# PCD-disc-schematic.net
KiCad netlist of a schematic drawn in Altium Designer
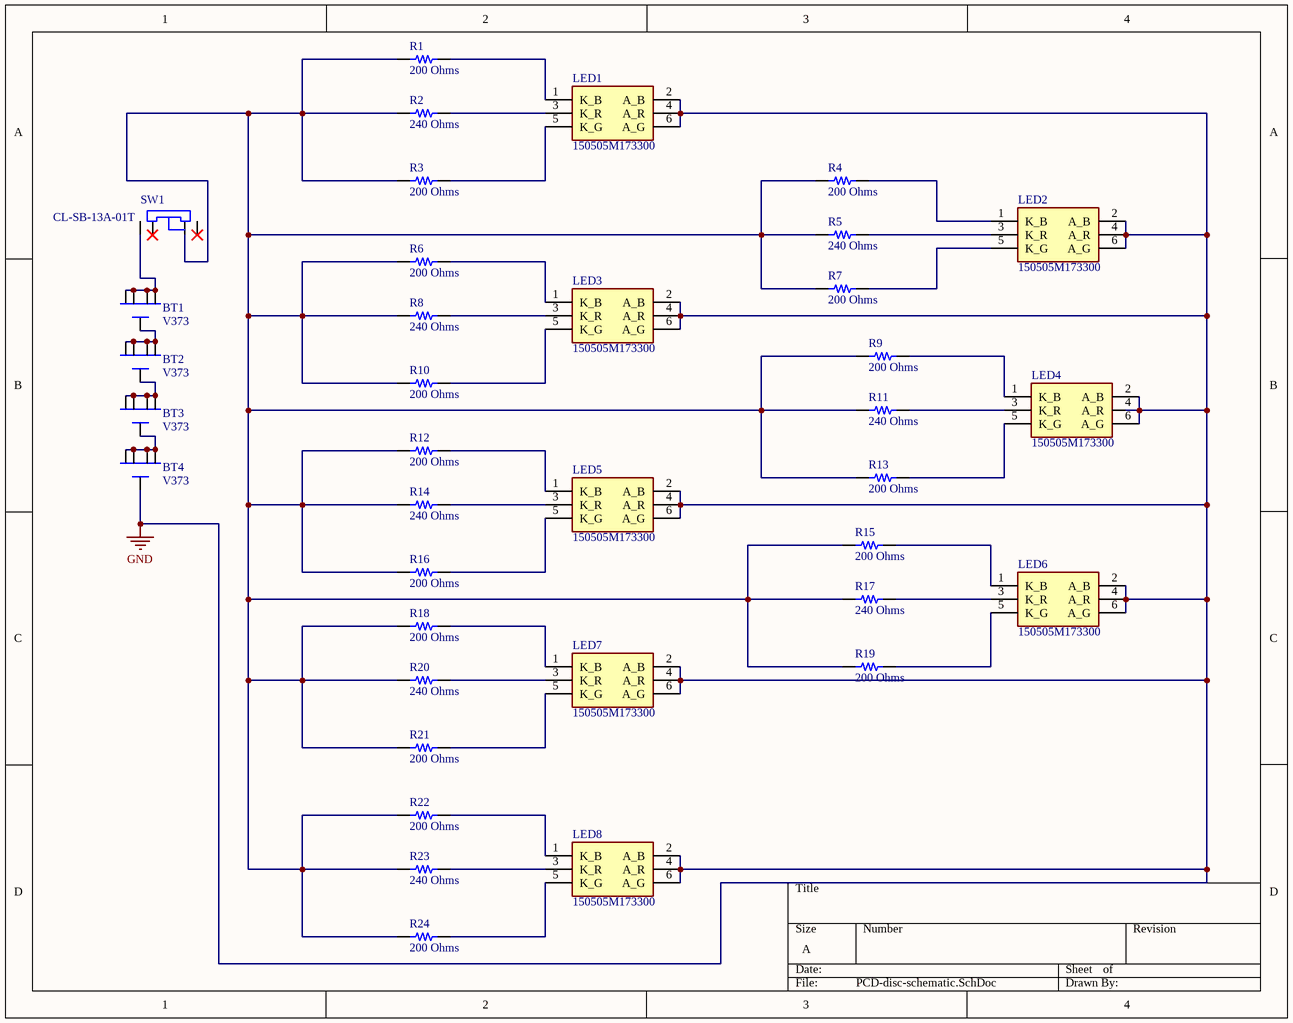
[diagram p0: PCD-disc-schematic.SchDoc]

(export (version "E")
  (design (tool "Eeschema 10.0.6"))
  (components
    (comp (ref "BT1") (value "V373") (footprint "V373") (libsource (lib "PCD-lib") (part "V373")))
    (comp (ref "BT2") (value "V373") (footprint "V373") (libsource (lib "PCD-lib") (part "V373")))
    (comp (ref "BT3") (value "V373") (footprint "V373") (libsource (lib "PCD-lib") (part "V373")))
    (comp (ref "BT4") (value "V373") (footprint "V373") (libsource (lib "PCD-lib") (part "V373")))
    (comp (ref "LED1")
      (value "150505M173300")
      (footprint "SamacSys:150505M173300")
      (description "LED")
      (fields (field (name "MOUSER PART NUMBER") "710-150505M173300"))
      (libsource (lib "*") (part "150505M173300"))
    )
    (comp (ref "LED2")
      (value "150505M173300")
      (footprint "SamacSys:150505M173300")
      (description "LED")
      (fields (field (name "MOUSER PART NUMBER") "710-150505M173300"))
      (libsource (lib "*") (part "150505M173300"))
    )
    (comp (ref "LED3")
      (value "150505M173300")
      (footprint "SamacSys:150505M173300")
      (description "LED")
      (fields (field (name "MOUSER PART NUMBER") "710-150505M173300"))
      (libsource (lib "*") (part "150505M173300"))
    )
    (comp (ref "LED4")
      (value "150505M173300")
      (footprint "SamacSys:150505M173300")
      (description "LED")
      (fields (field (name "MOUSER PART NUMBER") "710-150505M173300"))
      (libsource (lib "*") (part "150505M173300"))
    )
    (comp (ref "LED5")
      (value "150505M173300")
      (footprint "SamacSys:150505M173300")
      (description "LED")
      (fields (field (name "MOUSER PART NUMBER") "710-150505M173300"))
      (libsource (lib "*") (part "150505M173300"))
    )
    (comp (ref "LED6")
      (value "150505M173300")
      (footprint "SamacSys:150505M173300")
      (description "LED")
      (fields (field (name "MOUSER PART NUMBER") "710-150505M173300"))
      (libsource (lib "*") (part "150505M173300"))
    )
    (comp (ref "LED7")
      (value "150505M173300")
      (footprint "SamacSys:150505M173300")
      (description "LED")
      (fields (field (name "MOUSER PART NUMBER") "710-150505M173300"))
      (libsource (lib "*") (part "150505M173300"))
    )
    (comp (ref "LED8")
      (value "150505M173300")
      (footprint "SamacSys:150505M173300")
      (description "LED")
      (fields (field (name "MOUSER PART NUMBER") "710-150505M173300"))
      (libsource (lib "*") (part "150505M173300"))
    )
    (comp (ref "R1")
      (value "200 Ohms")
      (footprint "RES 0603_1608")
      (description "RES 200 OHM 1% 1/10W 0603")
      (fields (field (name "PART NUMBER") "CRCW0603200RFKEAC") (field (name "MANUFACTURER") "Vishay Dale"))
      (libsource (lib "Celestial Altium Library - altium_library") (part "Resistor"))
    )
    (comp (ref "R2")
      (value "240 Ohms")
      (footprint "RES 0603_1608")
      (description "RES 240 OHM 1% 1/10W 0603")
      (fields
        (field (name "PART NUMBER") "RMCF0603FT240R")
        (field (name "MANUFACTURER") "Stackpole Electronics Inc")
      )
      (libsource (lib "Celestial Altium Library - altium_library") (part "Resistor"))
    )
    (comp (ref "R3")
      (value "200 Ohms")
      (footprint "RES 0603_1608")
      (description "RES 200 OHM 1% 1/10W 0603")
      (fields (field (name "PART NUMBER") "CRCW0603200RFKEAC") (field (name "MANUFACTURER") "Vishay Dale"))
      (libsource (lib "Celestial Altium Library - altium_library") (part "Resistor"))
    )
    (comp (ref "R4")
      (value "200 Ohms")
      (footprint "RES 0603_1608")
      (description "RES 200 OHM 1% 1/10W 0603")
      (fields (field (name "PART NUMBER") "CRCW0603200RFKEAC") (field (name "MANUFACTURER") "Vishay Dale"))
      (libsource (lib "Celestial Altium Library - altium_library") (part "Resistor"))
    )
    (comp (ref "R5")
      (value "240 Ohms")
      (footprint "RES 0603_1608")
      (description "RES 240 OHM 1% 1/10W 0603")
      (fields
        (field (name "PART NUMBER") "RMCF0603FT240R")
        (field (name "MANUFACTURER") "Stackpole Electronics Inc")
      )
      (libsource (lib "Celestial Altium Library - altium_library") (part "Resistor"))
    )
    (comp (ref "R6")
      (value "200 Ohms")
      (footprint "RES 0603_1608")
      (description "RES 200 OHM 1% 1/10W 0603")
      (fields (field (name "PART NUMBER") "CRCW0603200RFKEAC") (field (name "MANUFACTURER") "Vishay Dale"))
      (libsource (lib "Celestial Altium Library - altium_library") (part "Resistor"))
    )
    (comp (ref "R7")
      (value "200 Ohms")
      (footprint "RES 0603_1608")
      (description "RES 200 OHM 1% 1/10W 0603")
      (fields (field (name "PART NUMBER") "CRCW0603200RFKEAC") (field (name "MANUFACTURER") "Vishay Dale"))
      (libsource (lib "Celestial Altium Library - altium_library") (part "Resistor"))
    )
    (comp (ref "R8")
      (value "240 Ohms")
      (footprint "RES 0603_1608")
      (description "RES 240 OHM 1% 1/10W 0603")
      (fields
        (field (name "PART NUMBER") "RMCF0603FT240R")
        (field (name "MANUFACTURER") "Stackpole Electronics Inc")
      )
      (libsource (lib "Celestial Altium Library - altium_library") (part "Resistor"))
    )
    (comp (ref "R9")
      (value "200 Ohms")
      (footprint "RES 0603_1608")
      (description "RES 200 OHM 1% 1/10W 0603")
      (fields (field (name "PART NUMBER") "CRCW0603200RFKEAC") (field (name "MANUFACTURER") "Vishay Dale"))
      (libsource (lib "Celestial Altium Library - altium_library") (part "Resistor"))
    )
    (comp (ref "R10")
      (value "200 Ohms")
      (footprint "RES 0603_1608")
      (description "RES 200 OHM 1% 1/10W 0603")
      (fields (field (name "PART NUMBER") "CRCW0603200RFKEAC") (field (name "MANUFACTURER") "Vishay Dale"))
      (libsource (lib "Celestial Altium Library - altium_library") (part "Resistor"))
    )
    (comp (ref "R11")
      (value "240 Ohms")
      (footprint "RES 0603_1608")
      (description "RES 240 OHM 1% 1/10W 0603")
      (fields
        (field (name "PART NUMBER") "RMCF0603FT240R")
        (field (name "MANUFACTURER") "Stackpole Electronics Inc")
      )
      (libsource (lib "Celestial Altium Library - altium_library") (part "Resistor"))
    )
    (comp (ref "R12")
      (value "200 Ohms")
      (footprint "RES 0603_1608")
      (description "RES 200 OHM 1% 1/10W 0603")
      (fields (field (name "PART NUMBER") "CRCW0603200RFKEAC") (field (name "MANUFACTURER") "Vishay Dale"))
      (libsource (lib "Celestial Altium Library - altium_library") (part "Resistor"))
    )
    (comp (ref "R13")
      (value "200 Ohms")
      (footprint "RES 0603_1608")
      (description "RES 200 OHM 1% 1/10W 0603")
      (fields (field (name "PART NUMBER") "CRCW0603200RFKEAC") (field (name "MANUFACTURER") "Vishay Dale"))
      (libsource (lib "Celestial Altium Library - altium_library") (part "Resistor"))
    )
    (comp (ref "R14")
      (value "240 Ohms")
      (footprint "RES 0603_1608")
      (description "RES 240 OHM 1% 1/10W 0603")
      (fields
        (field (name "PART NUMBER") "RMCF0603FT240R")
        (field (name "MANUFACTURER") "Stackpole Electronics Inc")
      )
      (libsource (lib "Celestial Altium Library - altium_library") (part "Resistor"))
    )
    (comp (ref "R15")
      (value "200 Ohms")
      (footprint "RES 0603_1608")
      (description "RES 200 OHM 1% 1/10W 0603")
      (fields (field (name "PART NUMBER") "CRCW0603200RFKEAC") (field (name "MANUFACTURER") "Vishay Dale"))
      (libsource (lib "Celestial Altium Library - altium_library") (part "Resistor"))
    )
    (comp (ref "R16")
      (value "200 Ohms")
      (footprint "RES 0603_1608")
      (description "RES 200 OHM 1% 1/10W 0603")
      (fields (field (name "PART NUMBER") "CRCW0603200RFKEAC") (field (name "MANUFACTURER") "Vishay Dale"))
      (libsource (lib "Celestial Altium Library - altium_library") (part "Resistor"))
    )
    (comp (ref "R17")
      (value "240 Ohms")
      (footprint "RES 0603_1608")
      (description "RES 240 OHM 1% 1/10W 0603")
      (fields
        (field (name "PART NUMBER") "RMCF0603FT240R")
        (field (name "MANUFACTURER") "Stackpole Electronics Inc")
      )
      (libsource (lib "Celestial Altium Library - altium_library") (part "Resistor"))
    )
    (comp (ref "R18")
      (value "200 Ohms")
      (footprint "RES 0603_1608")
      (description "RES 200 OHM 1% 1/10W 0603")
      (fields (field (name "PART NUMBER") "CRCW0603200RFKEAC") (field (name "MANUFACTURER") "Vishay Dale"))
      (libsource (lib "Celestial Altium Library - altium_library") (part "Resistor"))
    )
    (comp (ref "R19")
      (value "200 Ohms")
      (footprint "RES 0603_1608")
      (description "RES 200 OHM 1% 1/10W 0603")
      (fields (field (name "PART NUMBER") "CRCW0603200RFKEAC") (field (name "MANUFACTURER") "Vishay Dale"))
      (libsource (lib "Celestial Altium Library - altium_library") (part "Resistor"))
    )
    (comp (ref "R20")
      (value "240 Ohms")
      (footprint "RES 0603_1608")
      (description "RES 240 OHM 1% 1/10W 0603")
      (fields
        (field (name "PART NUMBER") "RMCF0603FT240R")
        (field (name "MANUFACTURER") "Stackpole Electronics Inc")
      )
      (libsource (lib "Celestial Altium Library - altium_library") (part "Resistor"))
    )
    (comp (ref "R21")
      (value "200 Ohms")
      (footprint "RES 0603_1608")
      (description "RES 200 OHM 1% 1/10W 0603")
      (fields (field (name "PART NUMBER") "CRCW0603200RFKEAC") (field (name "MANUFACTURER") "Vishay Dale"))
      (libsource (lib "Celestial Altium Library - altium_library") (part "Resistor"))
    )
    (comp (ref "R22")
      (value "200 Ohms")
      (footprint "RES 0603_1608")
      (description "RES 200 OHM 1% 1/10W 0603")
      (fields (field (name "PART NUMBER") "CRCW0603200RFKEAC") (field (name "MANUFACTURER") "Vishay Dale"))
      (libsource (lib "Celestial Altium Library - altium_library") (part "Resistor"))
    )
    (comp (ref "R23")
      (value "240 Ohms")
      (footprint "RES 0603_1608")
      (description "RES 240 OHM 1% 1/10W 0603")
      (fields
        (field (name "PART NUMBER") "RMCF0603FT240R")
        (field (name "MANUFACTURER") "Stackpole Electronics Inc")
      )
      (libsource (lib "Celestial Altium Library - altium_library") (part "Resistor"))
    )
    (comp (ref "R24")
      (value "200 Ohms")
      (footprint "RES 0603_1608")
      (description "RES 200 OHM 1% 1/10W 0603")
      (fields (field (name "PART NUMBER") "CRCW0603200RFKEAC") (field (name "MANUFACTURER") "Vishay Dale"))
      (libsource (lib "Celestial Altium Library - altium_library") (part "Resistor"))
    )
    (comp (ref "SW1")
      (value "CL-SB-13A-01T")
      (footprint "CL-SB-13A-01T")
      (description "SWITCH SLIDE SP3T 200MA 12V")
      (libsource (lib "PCD-lib") (part "CL-SB-13A-01T"))
    )
  )
  (nets
    (net (code "1") (name "GND") (class "Default")
      (node (ref "BT4") (pin "5") (pinfunction "5_5") (pintype "passive"))
      (node (ref "LED1") (pin "2") (pinfunction "A_B_2") (pintype "passive"))
      (node (ref "LED1") (pin "4") (pinfunction "A_R_4") (pintype "passive"))
      (node (ref "LED1") (pin "6") (pinfunction "A_G_6") (pintype "passive"))
      (node (ref "LED2") (pin "2") (pinfunction "A_B_2") (pintype "passive"))
      (node (ref "LED2") (pin "4") (pinfunction "A_R_4") (pintype "passive"))
      (node (ref "LED2") (pin "6") (pinfunction "A_G_6") (pintype "passive"))
      (node (ref "LED3") (pin "2") (pinfunction "A_B_2") (pintype "passive"))
      (node (ref "LED3") (pin "4") (pinfunction "A_R_4") (pintype "passive"))
      (node (ref "LED3") (pin "6") (pinfunction "A_G_6") (pintype "passive"))
      (node (ref "LED4") (pin "2") (pinfunction "A_B_2") (pintype "passive"))
      (node (ref "LED4") (pin "4") (pinfunction "A_R_4") (pintype "passive"))
      (node (ref "LED4") (pin "6") (pinfunction "A_G_6") (pintype "passive"))
      (node (ref "LED5") (pin "2") (pinfunction "A_B_2") (pintype "passive"))
      (node (ref "LED5") (pin "4") (pinfunction "A_R_4") (pintype "passive"))
      (node (ref "LED5") (pin "6") (pinfunction "A_G_6") (pintype "passive"))
      (node (ref "LED6") (pin "2") (pinfunction "A_B_2") (pintype "passive"))
      (node (ref "LED6") (pin "4") (pinfunction "A_R_4") (pintype "passive"))
      (node (ref "LED6") (pin "6") (pinfunction "A_G_6") (pintype "passive"))
      (node (ref "LED7") (pin "2") (pinfunction "A_B_2") (pintype "passive"))
      (node (ref "LED7") (pin "4") (pinfunction "A_R_4") (pintype "passive"))
      (node (ref "LED7") (pin "6") (pinfunction "A_G_6") (pintype "passive"))
      (node (ref "LED8") (pin "2") (pinfunction "A_B_2") (pintype "passive"))
      (node (ref "LED8") (pin "4") (pinfunction "A_R_4") (pintype "passive"))
      (node (ref "LED8") (pin "6") (pinfunction "A_G_6") (pintype "passive"))
    )
    (net (code "2") (name "Net-(BT1-Pad1)") (class "Default")
      (node (ref "BT1") (pin "1") (pinfunction "1_1") (pintype "passive"))
      (node (ref "BT1") (pin "2") (pinfunction "2_2") (pintype "passive"))
      (node (ref "BT1") (pin "3") (pinfunction "3_3") (pintype "passive"))
      (node (ref "BT1") (pin "4") (pinfunction "4_4") (pintype "passive"))
      (node (ref "SW1") (pin "1") (pinfunction "1_1") (pintype "passive"))
    )
    (net (code "3") (name "Net-(BT1-Pad5)") (class "Default")
      (node (ref "BT1") (pin "5") (pinfunction "5_5") (pintype "passive"))
      (node (ref "BT2") (pin "1") (pinfunction "1_1") (pintype "passive"))
      (node (ref "BT2") (pin "2") (pinfunction "2_2") (pintype "passive"))
      (node (ref "BT2") (pin "3") (pinfunction "3_3") (pintype "passive"))
      (node (ref "BT2") (pin "4") (pinfunction "4_4") (pintype "passive"))
    )
    (net (code "4") (name "Net-(BT2-Pad5)") (class "Default")
      (node (ref "BT2") (pin "5") (pinfunction "5_5") (pintype "passive"))
      (node (ref "BT3") (pin "1") (pinfunction "1_1") (pintype "passive"))
      (node (ref "BT3") (pin "2") (pinfunction "2_2") (pintype "passive"))
      (node (ref "BT3") (pin "3") (pinfunction "3_3") (pintype "passive"))
      (node (ref "BT3") (pin "4") (pinfunction "4_4") (pintype "passive"))
    )
    (net (code "5") (name "Net-(BT3-Pad5)") (class "Default")
      (node (ref "BT3") (pin "5") (pinfunction "5_5") (pintype "passive"))
      (node (ref "BT4") (pin "1") (pinfunction "1_1") (pintype "passive"))
      (node (ref "BT4") (pin "2") (pinfunction "2_2") (pintype "passive"))
      (node (ref "BT4") (pin "3") (pinfunction "3_3") (pintype "passive"))
      (node (ref "BT4") (pin "4") (pinfunction "4_4") (pintype "passive"))
    )
    (net (code "6") (name "Net-(LED1-K_B)") (class "Default")
      (node (ref "LED1") (pin "1") (pinfunction "K_B_1") (pintype "passive"))
      (node (ref "R1") (pin "2") (pinfunction "2_2") (pintype "passive"))
    )
    (net (code "7") (name "Net-(LED1-K_G)") (class "Default")
      (node (ref "LED1") (pin "5") (pinfunction "K_G_5") (pintype "passive"))
      (node (ref "R3") (pin "2") (pinfunction "2_2") (pintype "passive"))
    )
    (net (code "8") (name "Net-(LED1-K_R)") (class "Default")
      (node (ref "LED1") (pin "3") (pinfunction "K_R_3") (pintype "passive"))
      (node (ref "R2") (pin "2") (pinfunction "2_2") (pintype "passive"))
    )
    (net (code "9") (name "Net-(LED2-K_B)") (class "Default")
      (node (ref "LED2") (pin "1") (pinfunction "K_B_1") (pintype "passive"))
      (node (ref "R4") (pin "2") (pinfunction "2_2") (pintype "passive"))
    )
    (net (code "10") (name "Net-(LED2-K_G)") (class "Default")
      (node (ref "LED2") (pin "5") (pinfunction "K_G_5") (pintype "passive"))
      (node (ref "R7") (pin "2") (pinfunction "2_2") (pintype "passive"))
    )
    (net (code "11") (name "Net-(LED2-K_R)") (class "Default")
      (node (ref "LED2") (pin "3") (pinfunction "K_R_3") (pintype "passive"))
      (node (ref "R5") (pin "2") (pinfunction "2_2") (pintype "passive"))
    )
    (net (code "12") (name "Net-(LED3-K_B)") (class "Default")
      (node (ref "LED3") (pin "1") (pinfunction "K_B_1") (pintype "passive"))
      (node (ref "R6") (pin "2") (pinfunction "2_2") (pintype "passive"))
    )
    (net (code "13") (name "Net-(LED3-K_G)") (class "Default")
      (node (ref "LED3") (pin "5") (pinfunction "K_G_5") (pintype "passive"))
      (node (ref "R10") (pin "2") (pinfunction "2_2") (pintype "passive"))
    )
    (net (code "14") (name "Net-(LED3-K_R)") (class "Default")
      (node (ref "LED3") (pin "3") (pinfunction "K_R_3") (pintype "passive"))
      (node (ref "R8") (pin "2") (pinfunction "2_2") (pintype "passive"))
    )
    (net (code "15") (name "Net-(LED4-K_B)") (class "Default")
      (node (ref "LED4") (pin "1") (pinfunction "K_B_1") (pintype "passive"))
      (node (ref "R9") (pin "2") (pinfunction "2_2") (pintype "passive"))
    )
    (net (code "16") (name "Net-(LED4-K_G)") (class "Default")
      (node (ref "LED4") (pin "5") (pinfunction "K_G_5") (pintype "passive"))
      (node (ref "R13") (pin "2") (pinfunction "2_2") (pintype "passive"))
    )
    (net (code "17") (name "Net-(LED4-K_R)") (class "Default")
      (node (ref "LED4") (pin "3") (pinfunction "K_R_3") (pintype "passive"))
      (node (ref "R11") (pin "2") (pinfunction "2_2") (pintype "passive"))
    )
    (net (code "18") (name "Net-(LED5-K_B)") (class "Default")
      (node (ref "LED5") (pin "1") (pinfunction "K_B_1") (pintype "passive"))
      (node (ref "R12") (pin "2") (pinfunction "2_2") (pintype "passive"))
    )
    (net (code "19") (name "Net-(LED5-K_G)") (class "Default")
      (node (ref "LED5") (pin "5") (pinfunction "K_G_5") (pintype "passive"))
      (node (ref "R16") (pin "2") (pinfunction "2_2") (pintype "passive"))
    )
    (net (code "20") (name "Net-(LED5-K_R)") (class "Default")
      (node (ref "LED5") (pin "3") (pinfunction "K_R_3") (pintype "passive"))
      (node (ref "R14") (pin "2") (pinfunction "2_2") (pintype "passive"))
    )
    (net (code "21") (name "Net-(LED6-K_B)") (class "Default")
      (node (ref "LED6") (pin "1") (pinfunction "K_B_1") (pintype "passive"))
      (node (ref "R15") (pin "2") (pinfunction "2_2") (pintype "passive"))
    )
    (net (code "22") (name "Net-(LED6-K_G)") (class "Default")
      (node (ref "LED6") (pin "5") (pinfunction "K_G_5") (pintype "passive"))
      (node (ref "R19") (pin "2") (pinfunction "2_2") (pintype "passive"))
    )
    (net (code "23") (name "Net-(LED6-K_R)") (class "Default")
      (node (ref "LED6") (pin "3") (pinfunction "K_R_3") (pintype "passive"))
      (node (ref "R17") (pin "2") (pinfunction "2_2") (pintype "passive"))
    )
    (net (code "24") (name "Net-(LED7-K_B)") (class "Default")
      (node (ref "LED7") (pin "1") (pinfunction "K_B_1") (pintype "passive"))
      (node (ref "R18") (pin "2") (pinfunction "2_2") (pintype "passive"))
    )
    (net (code "25") (name "Net-(LED7-K_G)") (class "Default")
      (node (ref "LED7") (pin "5") (pinfunction "K_G_5") (pintype "passive"))
      (node (ref "R21") (pin "2") (pinfunction "2_2") (pintype "passive"))
    )
    (net (code "26") (name "Net-(LED7-K_R)") (class "Default")
      (node (ref "LED7") (pin "3") (pinfunction "K_R_3") (pintype "passive"))
      (node (ref "R20") (pin "2") (pinfunction "2_2") (pintype "passive"))
    )
    (net (code "27") (name "Net-(LED8-K_B)") (class "Default")
      (node (ref "LED8") (pin "1") (pinfunction "K_B_1") (pintype "passive"))
      (node (ref "R22") (pin "2") (pinfunction "2_2") (pintype "passive"))
    )
    (net (code "28") (name "Net-(LED8-K_G)") (class "Default")
      (node (ref "LED8") (pin "5") (pinfunction "K_G_5") (pintype "passive"))
      (node (ref "R24") (pin "2") (pinfunction "2_2") (pintype "passive"))
    )
    (net (code "29") (name "Net-(LED8-K_R)") (class "Default")
      (node (ref "LED8") (pin "3") (pinfunction "K_R_3") (pintype "passive"))
      (node (ref "R23") (pin "2") (pinfunction "2_2") (pintype "passive"))
    )
    (net (code "30") (name "Net-(R1-Pad1)") (class "Default")
      (node (ref "R1") (pin "1") (pinfunction "1_1") (pintype "passive"))
      (node (ref "R10") (pin "1") (pinfunction "1_1") (pintype "passive"))
      (node (ref "R11") (pin "1") (pinfunction "1_1") (pintype "passive"))
      (node (ref "R12") (pin "1") (pinfunction "1_1") (pintype "passive"))
      (node (ref "R13") (pin "1") (pinfunction "1_1") (pintype "passive"))
      (node (ref "R14") (pin "1") (pinfunction "1_1") (pintype "passive"))
      (node (ref "R15") (pin "1") (pinfunction "1_1") (pintype "passive"))
      (node (ref "R16") (pin "1") (pinfunction "1_1") (pintype "passive"))
      (node (ref "R17") (pin "1") (pinfunction "1_1") (pintype "passive"))
      (node (ref "R18") (pin "1") (pinfunction "1_1") (pintype "passive"))
      (node (ref "R19") (pin "1") (pinfunction "1_1") (pintype "passive"))
      (node (ref "R2") (pin "1") (pinfunction "1_1") (pintype "passive"))
      (node (ref "R20") (pin "1") (pinfunction "1_1") (pintype "passive"))
      (node (ref "R21") (pin "1") (pinfunction "1_1") (pintype "passive"))
      (node (ref "R22") (pin "1") (pinfunction "1_1") (pintype "passive"))
      (node (ref "R23") (pin "1") (pinfunction "1_1") (pintype "passive"))
      (node (ref "R24") (pin "1") (pinfunction "1_1") (pintype "passive"))
      (node (ref "R3") (pin "1") (pinfunction "1_1") (pintype "passive"))
      (node (ref "R4") (pin "1") (pinfunction "1_1") (pintype "passive"))
      (node (ref "R5") (pin "1") (pinfunction "1_1") (pintype "passive"))
      (node (ref "R6") (pin "1") (pinfunction "1_1") (pintype "passive"))
      (node (ref "R7") (pin "1") (pinfunction "1_1") (pintype "passive"))
      (node (ref "R8") (pin "1") (pinfunction "1_1") (pintype "passive"))
      (node (ref "R9") (pin "1") (pinfunction "1_1") (pintype "passive"))
      (node (ref "SW1") (pin "3") (pinfunction "3_3") (pintype "passive"))
    )
    (net (code "31") (name "unconnected-(SW1-Pad2)") (class "Default")
      (node (ref "SW1") (pin "2") (pinfunction "2_2") (pintype "passive+no_connect"))
    )
    (net (code "32") (name "unconnected-(SW1-Pad4)") (class "Default")
      (node (ref "SW1") (pin "4") (pinfunction "4_4") (pintype "passive+no_connect"))
    )
  )
)
